# Project_traffic.net
KiCad netlist of a schematic drawn in Altium Designer
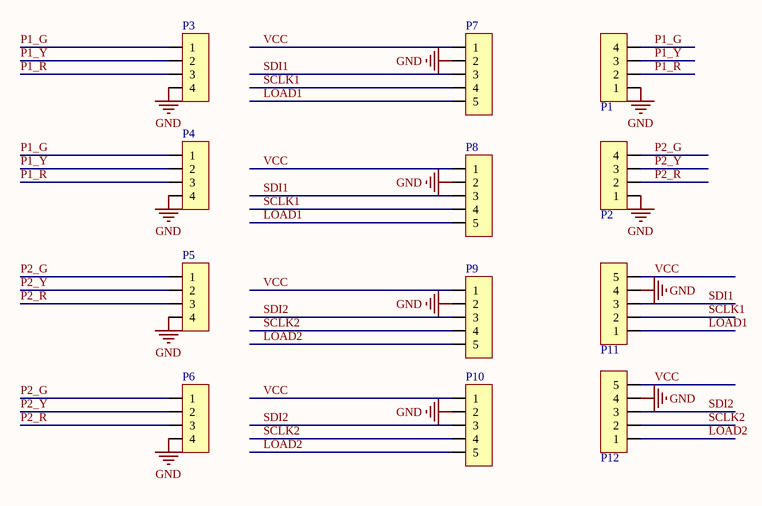
[diagram p0: Project_traffic.SchDoc]

(export (version "E")
  (design (tool "Eeschema 10.0.6"))
  (components
    (comp (ref "P1")
      (value "Header 4")
      (footprint "Header 4")
      (description "Header, 4-Pin")
      (libsource (lib "") (part "Header 4_1"))
    )
    (comp (ref "P2")
      (value "Header 4")
      (footprint "Header 4")
      (description "Header, 4-Pin")
      (libsource (lib "") (part "Header 4_1"))
    )
    (comp (ref "P3")
      (value "Header 4")
      (footprint "Header 4")
      (description "Header, 4-Pin")
      (libsource (lib "BKIT4U_LIB") (part "Header 4"))
    )
    (comp (ref "P4")
      (value "Header 4")
      (footprint "Header 4")
      (description "Header, 4-Pin")
      (libsource (lib "BKIT4U_LIB") (part "Header 4"))
    )
    (comp (ref "P5")
      (value "Header 4")
      (footprint "Header 4")
      (description "Header, 4-Pin")
      (libsource (lib "BKIT4U_LIB") (part "Header 4"))
    )
    (comp (ref "P6")
      (value "Header 4")
      (footprint "Header 4")
      (description "Header, 4-Pin")
      (libsource (lib "BKIT4U_LIB") (part "Header 4"))
    )
    (comp (ref "P7")
      (value "Header 5")
      (footprint "Header 5")
      (description "Header, 5-Pin")
      (fields (field (name "PUBLISHER") "Altium Limited"))
      (libsource (lib "") (part "Header 5_1"))
    )
    (comp (ref "P8")
      (value "Header 5")
      (footprint "Header 5")
      (description "Header, 5-Pin")
      (fields (field (name "PUBLISHER") "Altium Limited"))
      (libsource (lib "") (part "Header 5_1"))
    )
    (comp (ref "P9")
      (value "Header 5")
      (footprint "Header 5")
      (description "Header, 5-Pin")
      (fields (field (name "PUBLISHER") "Altium Limited"))
      (libsource (lib "") (part "Header 5_1"))
    )
    (comp (ref "P10")
      (value "Header 5")
      (footprint "Header 5")
      (description "Header, 5-Pin")
      (fields (field (name "PUBLISHER") "Altium Limited"))
      (libsource (lib "") (part "Header 5_1"))
    )
    (comp (ref "P11")
      (value "Header 5")
      (footprint "Header 5")
      (description "Header, 5-Pin")
      (fields (field (name "PUBLISHER") "Altium Limited"))
      (libsource (lib "BKIT4U_LIB") (part "Header 5"))
    )
    (comp (ref "P12")
      (value "Header 5")
      (footprint "Header 5")
      (description "Header, 5-Pin")
      (fields (field (name "PUBLISHER") "Altium Limited"))
      (libsource (lib "BKIT4U_LIB") (part "Header 5"))
    )
  )
  (nets
    (net (code "1") (name "/LOAD1") (class "Default")
      (node (ref "P11") (pin "1") (pinfunction "1_1") (pintype "passive"))
      (node (ref "P7") (pin "5") (pinfunction "5_5") (pintype "passive"))
      (node (ref "P8") (pin "5") (pinfunction "5_5") (pintype "passive"))
    )
    (net (code "2") (name "/LOAD2") (class "Default")
      (node (ref "P10") (pin "5") (pinfunction "5_5") (pintype "passive"))
      (node (ref "P12") (pin "1") (pinfunction "1_1") (pintype "passive"))
      (node (ref "P9") (pin "5") (pinfunction "5_5") (pintype "passive"))
    )
    (net (code "3") (name "/P1_G") (class "Default")
      (node (ref "P1") (pin "4") (pinfunction "4_4") (pintype "passive"))
      (node (ref "P3") (pin "1") (pinfunction "1_1") (pintype "passive"))
      (node (ref "P4") (pin "1") (pinfunction "1_1") (pintype "passive"))
    )
    (net (code "4") (name "/P1_R") (class "Default")
      (node (ref "P1") (pin "2") (pinfunction "2_2") (pintype "passive"))
      (node (ref "P3") (pin "3") (pinfunction "3_3") (pintype "passive"))
      (node (ref "P4") (pin "3") (pinfunction "3_3") (pintype "passive"))
    )
    (net (code "5") (name "/P1_Y") (class "Default")
      (node (ref "P1") (pin "3") (pinfunction "3_3") (pintype "passive"))
      (node (ref "P3") (pin "2") (pinfunction "2_2") (pintype "passive"))
      (node (ref "P4") (pin "2") (pinfunction "2_2") (pintype "passive"))
    )
    (net (code "6") (name "/P2_G") (class "Default")
      (node (ref "P2") (pin "4") (pinfunction "4_4") (pintype "passive"))
      (node (ref "P5") (pin "1") (pinfunction "1_1") (pintype "passive"))
      (node (ref "P6") (pin "1") (pinfunction "1_1") (pintype "passive"))
    )
    (net (code "7") (name "/P2_R") (class "Default")
      (node (ref "P2") (pin "2") (pinfunction "2_2") (pintype "passive"))
      (node (ref "P5") (pin "3") (pinfunction "3_3") (pintype "passive"))
      (node (ref "P6") (pin "3") (pinfunction "3_3") (pintype "passive"))
    )
    (net (code "8") (name "/P2_Y") (class "Default")
      (node (ref "P2") (pin "3") (pinfunction "3_3") (pintype "passive"))
      (node (ref "P5") (pin "2") (pinfunction "2_2") (pintype "passive"))
      (node (ref "P6") (pin "2") (pinfunction "2_2") (pintype "passive"))
    )
    (net (code "9") (name "/SCLK1") (class "Default")
      (node (ref "P11") (pin "2") (pinfunction "2_2") (pintype "passive"))
      (node (ref "P7") (pin "4") (pinfunction "4_4") (pintype "passive"))
      (node (ref "P8") (pin "4") (pinfunction "4_4") (pintype "passive"))
    )
    (net (code "10") (name "/SCLK2") (class "Default")
      (node (ref "P10") (pin "4") (pinfunction "4_4") (pintype "passive"))
      (node (ref "P12") (pin "2") (pinfunction "2_2") (pintype "passive"))
      (node (ref "P9") (pin "4") (pinfunction "4_4") (pintype "passive"))
    )
    (net (code "11") (name "/SDI1") (class "Default")
      (node (ref "P11") (pin "3") (pinfunction "3_3") (pintype "passive"))
      (node (ref "P7") (pin "3") (pinfunction "3_3") (pintype "passive"))
      (node (ref "P8") (pin "3") (pinfunction "3_3") (pintype "passive"))
    )
    (net (code "12") (name "/SDI2") (class "Default")
      (node (ref "P10") (pin "3") (pinfunction "3_3") (pintype "passive"))
      (node (ref "P12") (pin "3") (pinfunction "3_3") (pintype "passive"))
      (node (ref "P9") (pin "3") (pinfunction "3_3") (pintype "passive"))
    )
    (net (code "13") (name "/VCC") (class "Default")
      (node (ref "P10") (pin "1") (pinfunction "1_1") (pintype "passive"))
      (node (ref "P11") (pin "5") (pinfunction "5_5") (pintype "passive"))
      (node (ref "P12") (pin "5") (pinfunction "5_5") (pintype "passive"))
      (node (ref "P7") (pin "1") (pinfunction "1_1") (pintype "passive"))
      (node (ref "P8") (pin "1") (pinfunction "1_1") (pintype "passive"))
      (node (ref "P9") (pin "1") (pinfunction "1_1") (pintype "passive"))
    )
    (net (code "14") (name "GND") (class "Default")
      (node (ref "P1") (pin "1") (pinfunction "1_1") (pintype "passive"))
      (node (ref "P10") (pin "2") (pinfunction "2_2") (pintype "passive"))
      (node (ref "P11") (pin "4") (pinfunction "4_4") (pintype "passive"))
      (node (ref "P12") (pin "4") (pinfunction "4_4") (pintype "passive"))
      (node (ref "P2") (pin "1") (pinfunction "1_1") (pintype "passive"))
      (node (ref "P3") (pin "4") (pinfunction "4_4") (pintype "passive"))
      (node (ref "P4") (pin "4") (pinfunction "4_4") (pintype "passive"))
      (node (ref "P5") (pin "4") (pinfunction "4_4") (pintype "passive"))
      (node (ref "P6") (pin "4") (pinfunction "4_4") (pintype "passive"))
      (node (ref "P7") (pin "2") (pinfunction "2_2") (pintype "passive"))
      (node (ref "P8") (pin "2") (pinfunction "2_2") (pintype "passive"))
      (node (ref "P9") (pin "2") (pinfunction "2_2") (pintype "passive"))
    )
  )
)
